# MM_Button.net
KiCad netlist of a schematic drawn in EAGLE
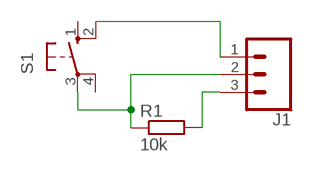
[diagram p0: schematic, sheet 1]

(export (version "E")
  (design (tool "Eeschema 10.0.6"))
  (components
    (comp (ref "J1")
      (value "CONN_03POLAR")
      (footprint "eagle-import:MOLEX-1X3")
      (libsource (lib "eagle-import") (part "CONN_03POLAR"))
    )
    (comp (ref "R1")
      (value "10k")
      (footprint "eagle-import:0204_7")
      (libsource (lib "eagle-import") (part "R-EU_0204/7"))
    )
    (comp (ref "S1")
      (value "10-XX")
      (footprint "eagle-import:B3F-10XX")
      (fields (field (name "MPN") "B3F-1000"))
      (libsource (lib "eagle-import") (part "10-XX"))
    )
  )
  (nets
    (net (code "1") (name "Net-(J1-Pad3)") (class "Default")
      (node (ref "J1") (pin "3") (pinfunction "3_3") (pintype "passive"))
      (node (ref "R1") (pin "2") (pinfunction "2_2") (pintype "passive"))
    )
    (net (code "2") (name "Net-(S1-P)") (class "Default")
      (node (ref "J1") (pin "2") (pinfunction "2_2") (pintype "passive"))
      (node (ref "R1") (pin "1") (pinfunction "1_1") (pintype "passive"))
      (node (ref "S1") (pin "3") (pinfunction "P_3") (pintype "passive"))
    )
    (net (code "3") (name "Net-(S1-S1)") (class "Default")
      (node (ref "J1") (pin "1") (pinfunction "1_1") (pintype "passive"))
      (node (ref "S1") (pin "2") (pinfunction "S1_2") (pintype "passive"))
    )
    (net (code "4") (name "unconnected-(S1-P1-Pad4)") (class "Default")
      (node (ref "S1") (pin "4") (pinfunction "P1_4") (pintype "passive"))
    )
    (net (code "5") (name "unconnected-(S1-S-Pad1)") (class "Default")
      (node (ref "S1") (pin "1") (pinfunction "S_1") (pintype "passive"))
    )
  )
)
